# Magnetometer.net
KiCad netlist of a schematic drawn in Altium Designer
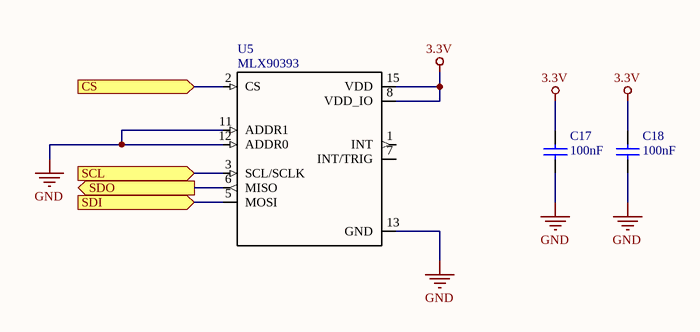
[diagram p0: Magnetometer.SchDoc]

(export (version "E")
  (design (tool "Eeschema 10.0.6"))
  (components
    (comp (ref "C17")
      (value "100nF")
      (footprint "0603 to 0805 SMD")
      (fields (field (name "Comment") "Cap"))
      (libsource (lib "RC0805FR-0751K1L") (part "Cap"))
    )
    (comp (ref "C18")
      (value "100nF")
      (footprint "0603 to 0805 SMD")
      (fields (field (name "Comment") "Cap"))
      (libsource (lib "RC0805FR-0751K1L") (part "Cap"))
    )
    (comp (ref "U5")
      (value "MLX90393")
      (footprint "QFN-16_WITH_AXIES")
      (description "Magnetometer (Compass)")
      (libsource (lib "AvionicsParts") (part "MLX90393"))
    )
  )
  (nets
    (net (code "1") (name "/CS") (class "Default")
      (node (ref "U5") (pin "2") (pinfunction "CS_2") (pintype "input"))
    )
    (net (code "2") (name "/SCL") (class "Default")
      (node (ref "U5") (pin "3") (pinfunction "SCL/SCLK_3") (pintype "input"))
    )
    (net (code "3") (name "/SDI") (class "Default")
      (node (ref "U5") (pin "5") (pinfunction "MOSI_5") (pintype "bidirectional"))
    )
    (net (code "4") (name "/SDO") (class "Default")
      (node (ref "U5") (pin "6") (pinfunction "MISO_6") (pintype "output"))
    )
    (net (code "5") (name "3.3V") (class "Default")
      (node (ref "C17") (pin "2") (pinfunction "2_2") (pintype "passive"))
      (node (ref "C18") (pin "2") (pinfunction "2_2") (pintype "passive"))
      (node (ref "U5") (pin "15") (pinfunction "VDD_15") (pintype "power_in"))
      (node (ref "U5") (pin "8") (pinfunction "VDD_IO_8") (pintype "power_in"))
    )
    (net (code "6") (name "GND") (class "Default")
      (node (ref "C17") (pin "1") (pinfunction "1_1") (pintype "passive"))
      (node (ref "C18") (pin "1") (pinfunction "1_1") (pintype "passive"))
      (node (ref "U5") (pin "11") (pinfunction "ADDR1_11") (pintype "input"))
      (node (ref "U5") (pin "12") (pinfunction "ADDR0_12") (pintype "input"))
      (node (ref "U5") (pin "13") (pinfunction "GND_13") (pintype "power_in"))
    )
    (net (code "7") (name "unconnected-(U5-INT-Pad1)") (class "Default")
      (node (ref "U5") (pin "1") (pinfunction "INT_1") (pintype "output"))
    )
    (net (code "8") (name "unconnected-(U5-INT{slash}TRIG-Pad7)") (class "Default")
      (node (ref "U5") (pin "7") (pinfunction "INT/TRIG_7") (pintype "bidirectional"))
    )
  )
)
